# motor_dora.net
KiCad netlist of a schematic drawn in EAGLE
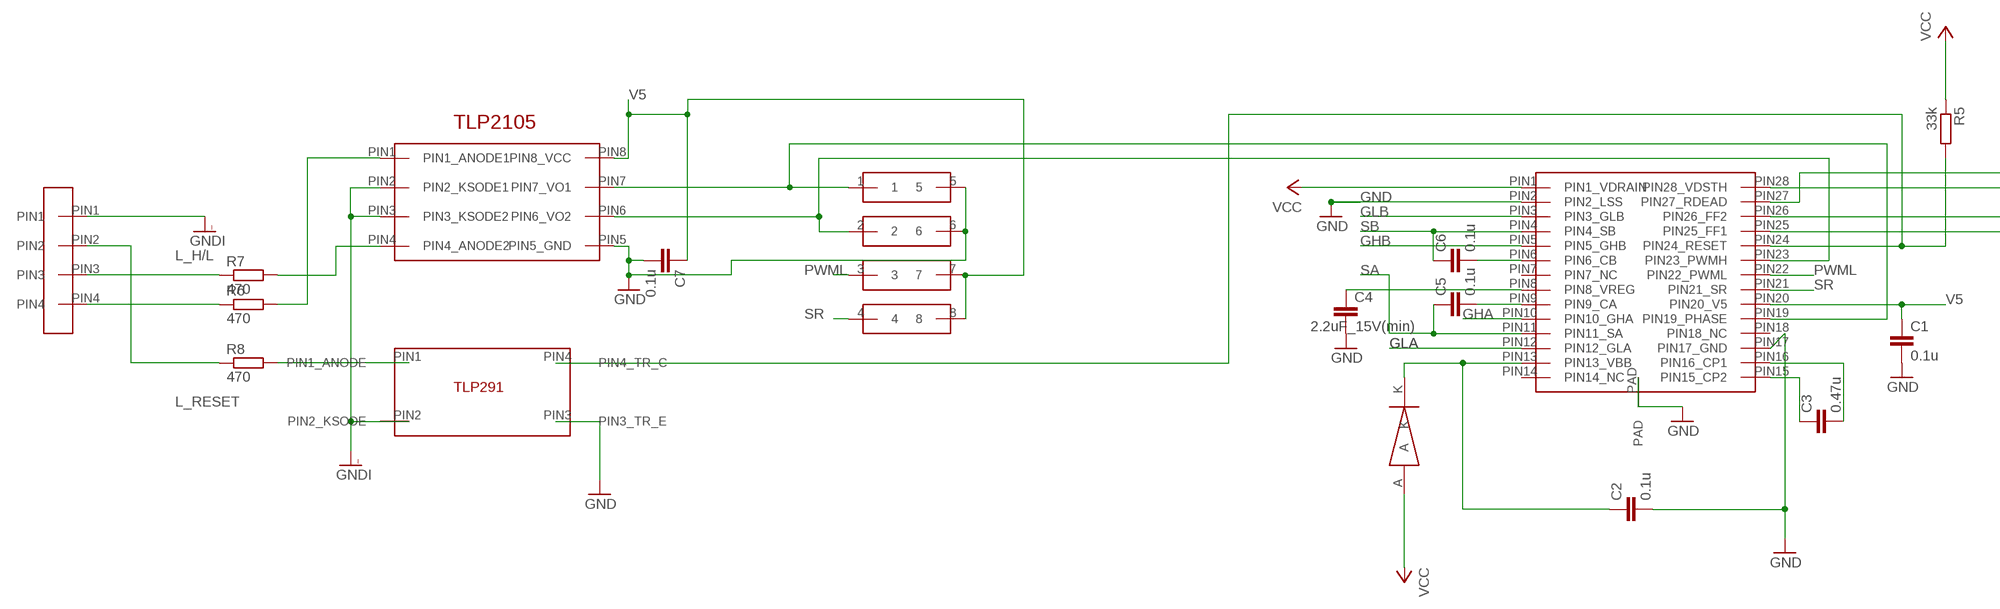
[diagram p0: schematic, sheet 1, part 1 of 2]
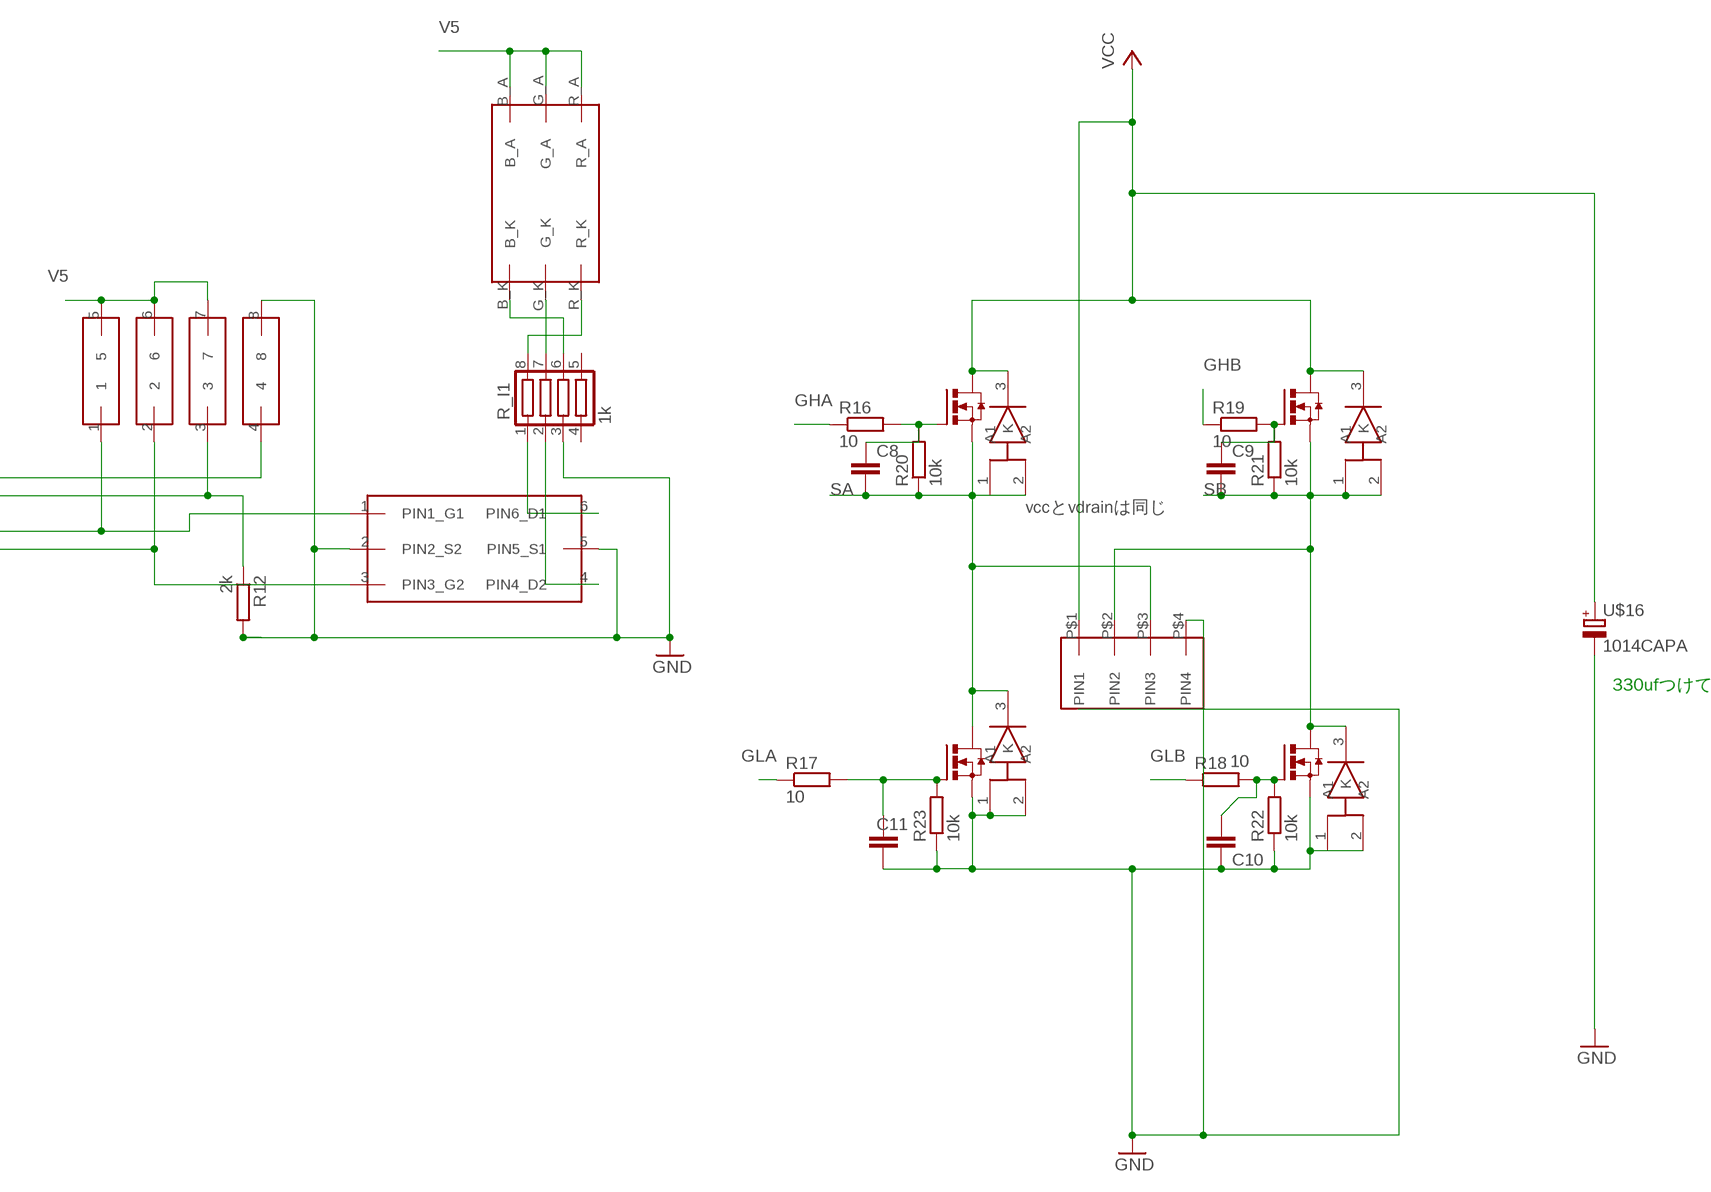
[diagram p1: schematic, sheet 1, part 2 of 2]

(export (version "E")
  (design (tool "Eeschema 10.0.6"))
  (components
    (comp (ref "C1")
      (value "0.1u")
      (footprint "eagle-import:C2012")
      (libsource (lib "eagle-import") (part "C-EUC2012"))
    )
    (comp (ref "C2")
      (value "0.1u")
      (footprint "eagle-import:C2012")
      (libsource (lib "eagle-import") (part "C-EUC2012"))
    )
    (comp (ref "C3")
      (value "0.47u")
      (footprint "eagle-import:C2012")
      (libsource (lib "eagle-import") (part "C-EUC2012"))
    )
    (comp (ref "C4")
      (value "2.2uF_15V(min)")
      (footprint "eagle-import:C2012")
      (libsource (lib "eagle-import") (part "C-EUC2012"))
    )
    (comp (ref "C5")
      (value "0.1u")
      (footprint "eagle-import:C2012")
      (libsource (lib "eagle-import") (part "C-EUC2012"))
    )
    (comp (ref "C6")
      (value "0.1u")
      (footprint "eagle-import:C2012")
      (libsource (lib "eagle-import") (part "C-EUC2012"))
    )
    (comp (ref "C7")
      (value "0.1u")
      (footprint "eagle-import:C2012")
      (libsource (lib "eagle-import") (part "C-EUC2012"))
    )
    (comp (ref "C8")
      (value "C-EUC2012")
      (footprint "eagle-import:C2012")
      (libsource (lib "eagle-import") (part "C-EUC2012"))
    )
    (comp (ref "C9")
      (value "C-EUC2012")
      (footprint "eagle-import:C2012")
      (libsource (lib "eagle-import") (part "C-EUC2012"))
    )
    (comp (ref "C10")
      (value "C-EUC2012")
      (footprint "eagle-import:C2012")
      (libsource (lib "eagle-import") (part "C-EUC2012"))
    )
    (comp (ref "C11")
      (value "C-EUC2012")
      (footprint "eagle-import:C2012")
      (libsource (lib "eagle-import") (part "C-EUC2012"))
    )
    (comp (ref "R5")
      (value "33k")
      (footprint "eagle-import:R2012")
      (libsource (lib "eagle-import") (part "R-EU_R2012"))
    )
    (comp (ref "R6")
      (value "470")
      (footprint "eagle-import:R2012")
      (libsource (lib "eagle-import") (part "R-EU_R2012"))
    )
    (comp (ref "R7")
      (value "470")
      (footprint "eagle-import:R2012")
      (libsource (lib "eagle-import") (part "R-EU_R2012"))
    )
    (comp (ref "R8")
      (value "470")
      (footprint "eagle-import:R2012")
      (libsource (lib "eagle-import") (part "R-EU_R2012"))
    )
    (comp (ref "R12")
      (value "2k")
      (footprint "eagle-import:R2012")
      (libsource (lib "eagle-import") (part "R-EU_R2012"))
    )
    (comp (ref "R16")
      (value "10")
      (footprint "eagle-import:R2012")
      (libsource (lib "eagle-import") (part "R-EU_R2012"))
    )
    (comp (ref "R17")
      (value "10")
      (footprint "eagle-import:R2012")
      (libsource (lib "eagle-import") (part "R-EU_R2012"))
    )
    (comp (ref "R18")
      (value "10")
      (footprint "eagle-import:R2012")
      (libsource (lib "eagle-import") (part "R-EU_R2012"))
    )
    (comp (ref "R19")
      (value "10")
      (footprint "eagle-import:R2012")
      (libsource (lib "eagle-import") (part "R-EU_R2012"))
    )
    (comp (ref "R20")
      (value "10k")
      (footprint "eagle-import:R2012")
      (libsource (lib "eagle-import") (part "R-EU_R2012"))
    )
    (comp (ref "R21")
      (value "10k")
      (footprint "eagle-import:R2012")
      (libsource (lib "eagle-import") (part "R-EU_R2012"))
    )
    (comp (ref "R22")
      (value "10k")
      (footprint "eagle-import:R2012")
      (libsource (lib "eagle-import") (part "R-EU_R2012"))
    )
    (comp (ref "R23")
      (value "10k")
      (footprint "eagle-import:R2012")
      (libsource (lib "eagle-import") (part "R-EU_R2012"))
    )
    (comp (ref "R_I1")
      (value "1k")
      (footprint "eagle-import:0603X4RESISTOR")
      (libsource (lib "eagle-import") (part "R_SHUGOU"))
    )
    (comp (ref "U$1")
      (value "A3921")
      (footprint "eagle-import:A3921")
      (libsource (lib "eagle-import") (part "A3921"))
    )
    (comp (ref "U$2")
      (value "TLP2105")
      (footprint "eagle-import:TLP2105")
      (libsource (lib "eagle-import") (part "TLP2105"))
    )
    (comp (ref "U$3")
      (value "TLP291")
      (footprint "eagle-import:TLP291")
      (libsource (lib "eagle-import") (part "TLP291"))
    )
    (comp (ref "U$4")
      (value "RGB_LED")
      (footprint "eagle-import:RGB_LED")
      (libsource (lib "eagle-import") (part "RGB_LED"))
    )
    (comp (ref "U$5")
      (value "10k")
      (footprint "eagle-import:1005X4RESISTOR")
      (libsource (lib "eagle-import") (part "1005X4RESISTOR"))
    )
    (comp (ref "U$6")
      (value "10k")
      (footprint "eagle-import:1005X4RESISTOR")
      (libsource (lib "eagle-import") (part "1005X4RESISTOR"))
    )
    (comp (ref "U$7")
      (value "SBR10M100P5Q")
      (footprint "eagle-import:POWERDI_5")
      (libsource (lib "eagle-import") (part "SBR10M100P5Q"))
    )
    (comp (ref "U$8")
      (value "IPD034N06N3G")
      (footprint "eagle-import:TO252")
      (libsource (lib "eagle-import") (part "IPD034N06N3G"))
    )
    (comp (ref "U$9")
      (value "IPD034N06N3G")
      (footprint "eagle-import:TO252")
      (libsource (lib "eagle-import") (part "IPD034N06N3G"))
    )
    (comp (ref "U$10")
      (value "IPD034N06N3G")
      (footprint "eagle-import:TO252")
      (libsource (lib "eagle-import") (part "IPD034N06N3G"))
    )
    (comp (ref "U$11")
      (value "IPD034N06N3G")
      (footprint "eagle-import:TO252")
      (libsource (lib "eagle-import") (part "IPD034N06N3G"))
    )
    (comp (ref "U$12")
      (value "SBR10M100P5Q")
      (footprint "eagle-import:POWERDI_5")
      (libsource (lib "eagle-import") (part "SBR10M100P5Q"))
    )
    (comp (ref "U$13")
      (value "DF1B_L_4P")
      (footprint "eagle-import:DF1B_L_4P")
      (libsource (lib "eagle-import") (part "DF1B_L_4P"))
    )
    (comp (ref "U$14")
      (value "VL_4P")
      (footprint "eagle-import:VL_4P")
      (libsource (lib "eagle-import") (part "VL_4P"))
    )
    (comp (ref "U$15")
      (value "SBR10M100P5Q")
      (footprint "eagle-import:POWERDI_5")
      (libsource (lib "eagle-import") (part "SBR10M100P5Q"))
    )
    (comp (ref "U$16")
      (value "1014CAPA")
      (footprint "eagle-import:1014CAPA")
      (libsource (lib "eagle-import") (part "1014CAPA"))
    )
    (comp (ref "U$17")
      (value "SMD_DAIOD")
      (footprint "eagle-import:SMD_DAIOD")
      (libsource (lib "eagle-import") (part "SMD_DAIOD"))
    )
    (comp (ref "U$18")
      (value "SSOT6_FET")
      (footprint "eagle-import:SSOT6_FET")
      (libsource (lib "eagle-import") (part "SSOT6_FET"))
    )
    (comp (ref "U$19")
      (value "SBR10M100P5Q")
      (footprint "eagle-import:POWERDI_5")
      (libsource (lib "eagle-import") (part "SBR10M100P5Q"))
    )
  )
  (nets
    (net (code "1") (name "/GHA") (class "Default")
      (node (ref "R16") (pin "1") (pinfunction "1_1") (pintype "passive"))
      (node (ref "U$1") (pin "PIN10") (pinfunction "PIN10_GHA_PIN10") (pintype "bidirectional"))
    )
    (net (code "2") (name "/GHB") (class "Default")
      (node (ref "R19") (pin "1") (pinfunction "1_1") (pintype "passive"))
      (node (ref "U$1") (pin "PIN5") (pinfunction "PIN5_GHB_PIN5") (pintype "bidirectional"))
    )
    (net (code "3") (name "/GLA") (class "Default")
      (node (ref "R17") (pin "1") (pinfunction "1_1") (pintype "passive"))
      (node (ref "U$1") (pin "PIN12") (pinfunction "PIN12_GLA_PIN12") (pintype "bidirectional"))
    )
    (net (code "4") (name "/GLB") (class "Default")
      (node (ref "R18") (pin "1") (pinfunction "1_1") (pintype "passive"))
      (node (ref "U$1") (pin "PIN3") (pinfunction "PIN3_GLB_PIN3") (pintype "bidirectional"))
    )
    (net (code "5") (name "/L_H{slash}L") (class "Default")
      (node (ref "R7") (pin "1") (pinfunction "1_1") (pintype "passive"))
      (node (ref "U$13") (pin "PIN3") (pinfunction "PIN3_PIN3") (pintype "bidirectional"))
    )
    (net (code "6") (name "/L_RESET") (class "Default")
      (node (ref "R8") (pin "1") (pinfunction "1_1") (pintype "passive"))
      (node (ref "U$13") (pin "PIN2") (pinfunction "PIN2_PIN2") (pintype "bidirectional"))
    )
    (net (code "7") (name "/PWML") (class "Default")
      (node (ref "U$1") (pin "PIN22") (pinfunction "PIN22_PWML_PIN22") (pintype "bidirectional"))
      (node (ref "U$5") (pin "3") (pinfunction "3_3") (pintype "bidirectional"))
    )
    (net (code "8") (name "/SA") (class "Default")
      (node (ref "C5") (pin "1") (pinfunction "1_1") (pintype "passive"))
      (node (ref "C8") (pin "2") (pinfunction "2_2") (pintype "passive"))
      (node (ref "R20") (pin "1") (pinfunction "1_1") (pintype "passive"))
      (node (ref "U$1") (pin "PIN11") (pinfunction "PIN11_SA_PIN11") (pintype "bidirectional"))
      (node (ref "U$10") (pin "PIN2") (pinfunction "PIN2_D_PIN2") (pintype "passive"))
      (node (ref "U$14") (pin "P$3") (pinfunction "PIN3_P$3") (pintype "bidirectional"))
      (node (ref "U$19") (pin "1") (pinfunction "A1_1") (pintype "bidirectional"))
      (node (ref "U$19") (pin "2") (pinfunction "A2_2") (pintype "bidirectional"))
      (node (ref "U$7") (pin "3") (pinfunction "K_3") (pintype "bidirectional"))
      (node (ref "U$8") (pin "PIN3") (pinfunction "PIN3_S_PIN3") (pintype "passive"))
    )
    (net (code "9") (name "/SB") (class "Default")
      (node (ref "C6") (pin "1") (pinfunction "1_1") (pintype "passive"))
      (node (ref "C9") (pin "2") (pinfunction "2_2") (pintype "passive"))
      (node (ref "R21") (pin "1") (pinfunction "1_1") (pintype "passive"))
      (node (ref "U$1") (pin "PIN4") (pinfunction "PIN4_SB_PIN4") (pintype "bidirectional"))
      (node (ref "U$11") (pin "PIN2") (pinfunction "PIN2_D_PIN2") (pintype "passive"))
      (node (ref "U$12") (pin "3") (pinfunction "K_3") (pintype "bidirectional"))
      (node (ref "U$14") (pin "P$2") (pinfunction "PIN2_P$2") (pintype "bidirectional"))
      (node (ref "U$15") (pin "1") (pinfunction "A1_1") (pintype "bidirectional"))
      (node (ref "U$15") (pin "2") (pinfunction "A2_2") (pintype "bidirectional"))
      (node (ref "U$9") (pin "PIN3") (pinfunction "PIN3_S_PIN3") (pintype "passive"))
    )
    (net (code "10") (name "/SR") (class "Default")
      (node (ref "U$1") (pin "PIN21") (pinfunction "PIN21_SR_PIN21") (pintype "bidirectional"))
      (node (ref "U$5") (pin "4") (pinfunction "4_4") (pintype "bidirectional"))
    )
    (net (code "11") (name "/V5") (class "Default")
      (node (ref "C1") (pin "1") (pinfunction "1_1") (pintype "passive"))
      (node (ref "C7") (pin "1") (pinfunction "1_1") (pintype "passive"))
      (node (ref "U$1") (pin "PIN20") (pinfunction "PIN20_V5_PIN20") (pintype "bidirectional"))
      (node (ref "U$2") (pin "PIN8") (pinfunction "PIN8_VCC_PIN8") (pintype "bidirectional"))
      (node (ref "U$4") (pin "B_A") (pinfunction "B_A_B_A") (pintype "bidirectional"))
      (node (ref "U$4") (pin "G_A") (pinfunction "G_A_G_A") (pintype "bidirectional"))
      (node (ref "U$4") (pin "R_A") (pinfunction "R_A_R_A") (pintype "bidirectional"))
      (node (ref "U$5") (pin "7") (pinfunction "7_7") (pintype "bidirectional"))
      (node (ref "U$5") (pin "8") (pinfunction "8_8") (pintype "bidirectional"))
      (node (ref "U$6") (pin "5") (pinfunction "5_5") (pintype "bidirectional"))
      (node (ref "U$6") (pin "6") (pinfunction "6_6") (pintype "bidirectional"))
      (node (ref "U$6") (pin "7") (pinfunction "7_7") (pintype "bidirectional"))
    )
    (net (code "12") (name "GND") (class "Default")
      (node (ref "C1") (pin "2") (pinfunction "2_2") (pintype "passive"))
      (node (ref "C10") (pin "2") (pinfunction "2_2") (pintype "passive"))
      (node (ref "C11") (pin "2") (pinfunction "2_2") (pintype "passive"))
      (node (ref "C2") (pin "2") (pinfunction "2_2") (pintype "passive"))
      (node (ref "C4") (pin "2") (pinfunction "2_2") (pintype "passive"))
      (node (ref "C7") (pin "2") (pinfunction "2_2") (pintype "passive"))
      (node (ref "R12") (pin "2") (pinfunction "2_2") (pintype "passive"))
      (node (ref "R22") (pin "1") (pinfunction "1_1") (pintype "passive"))
      (node (ref "R23") (pin "1") (pinfunction "1_1") (pintype "passive"))
      (node (ref "R_I1") (pin "3") (pinfunction "3_3") (pintype "passive"))
      (node (ref "U$1") (pin "PAD") (pinfunction "PAD_PAD") (pintype "bidirectional"))
      (node (ref "U$1") (pin "PIN17") (pinfunction "PIN17_GND_PIN17") (pintype "bidirectional"))
      (node (ref "U$1") (pin "PIN2") (pinfunction "PIN2_LSS_PIN2") (pintype "bidirectional"))
      (node (ref "U$10") (pin "PIN3") (pinfunction "PIN3_S_PIN3") (pintype "passive"))
      (node (ref "U$11") (pin "PIN3") (pinfunction "PIN3_S_PIN3") (pintype "passive"))
      (node (ref "U$12") (pin "1") (pinfunction "A1_1") (pintype "bidirectional"))
      (node (ref "U$12") (pin "2") (pinfunction "A2_2") (pintype "bidirectional"))
      (node (ref "U$14") (pin "P$4") (pinfunction "PIN4_P$4") (pintype "bidirectional"))
      (node (ref "U$16") (pin "-") (pinfunction "-_-") (pintype "passive"))
      (node (ref "U$18") (pin "2") (pinfunction "PIN2_S2_2") (pintype "bidirectional"))
      (node (ref "U$18") (pin "5") (pinfunction "PIN5_S1_5") (pintype "bidirectional"))
      (node (ref "U$2") (pin "PIN5") (pinfunction "PIN5_GND_PIN5") (pintype "bidirectional"))
      (node (ref "U$3") (pin "PIN3") (pinfunction "PIN3_TR_E_PIN3") (pintype "bidirectional"))
      (node (ref "U$5") (pin "5") (pinfunction "5_5") (pintype "bidirectional"))
      (node (ref "U$5") (pin "6") (pinfunction "6_6") (pintype "bidirectional"))
      (node (ref "U$6") (pin "8") (pinfunction "8_8") (pintype "bidirectional"))
      (node (ref "U$7") (pin "1") (pinfunction "A1_1") (pintype "bidirectional"))
      (node (ref "U$7") (pin "2") (pinfunction "A2_2") (pintype "bidirectional"))
    )
    (net (code "13") (name "GNDI") (class "Default")
      (node (ref "U$13") (pin "PIN1") (pinfunction "PIN1_PIN1") (pintype "bidirectional"))
      (node (ref "U$2") (pin "PIN2") (pinfunction "PIN2_KSODE1_PIN2") (pintype "bidirectional"))
      (node (ref "U$2") (pin "PIN3") (pinfunction "PIN3_KSODE2_PIN3") (pintype "bidirectional"))
      (node (ref "U$3") (pin "PIN2") (pinfunction "PIN2_KSODE_PIN2") (pintype "bidirectional"))
    )
    (net (code "14") (name "Net-(R6-Pad1)") (class "Default")
      (node (ref "R6") (pin "1") (pinfunction "1_1") (pintype "passive"))
      (node (ref "U$13") (pin "PIN4") (pinfunction "PIN4_PIN4") (pintype "bidirectional"))
    )
    (net (code "15") (name "Net-(R_I1-Pad6)") (class "Default")
      (node (ref "R_I1") (pin "6") (pinfunction "6_6") (pintype "passive"))
      (node (ref "U$4") (pin "B_K") (pinfunction "B_K_B_K") (pintype "bidirectional"))
    )
    (net (code "16") (name "Net-(R_I1-Pad7)") (class "Default")
      (node (ref "R_I1") (pin "7") (pinfunction "7_7") (pintype "passive"))
      (node (ref "U$4") (pin "G_K") (pinfunction "G_K_G_K") (pintype "bidirectional"))
    )
    (net (code "17") (name "Net-(R_I1-Pad8)") (class "Default")
      (node (ref "R_I1") (pin "8") (pinfunction "8_8") (pintype "passive"))
      (node (ref "U$4") (pin "R_K") (pinfunction "R_K_R_K") (pintype "bidirectional"))
    )
    (net (code "18") (name "Net-(U$1-PIN6_CB)") (class "Default")
      (node (ref "C6") (pin "2") (pinfunction "2_2") (pintype "passive"))
      (node (ref "U$1") (pin "PIN6") (pinfunction "PIN6_CB_PIN6") (pintype "bidirectional"))
    )
    (net (code "19") (name "Net-(U$1-PIN8_VREG)") (class "Default")
      (node (ref "C4") (pin "1") (pinfunction "1_1") (pintype "passive"))
      (node (ref "U$1") (pin "PIN8") (pinfunction "PIN8_VREG_PIN8") (pintype "bidirectional"))
    )
    (net (code "20") (name "Net-(U$1-PIN9_CA)") (class "Default")
      (node (ref "C5") (pin "2") (pinfunction "2_2") (pintype "passive"))
      (node (ref "U$1") (pin "PIN9") (pinfunction "PIN9_CA_PIN9") (pintype "bidirectional"))
    )
    (net (code "21") (name "Net-(U$1-PIN13_VBB)") (class "Default")
      (node (ref "C2") (pin "1") (pinfunction "1_1") (pintype "passive"))
      (node (ref "U$1") (pin "PIN13") (pinfunction "PIN13_VBB_PIN13") (pintype "bidirectional"))
      (node (ref "U$17") (pin "K") (pinfunction "K_K") (pintype "bidirectional"))
    )
    (net (code "22") (name "Net-(U$1-PIN15_CP2)") (class "Default")
      (node (ref "C3") (pin "1") (pinfunction "1_1") (pintype "passive"))
      (node (ref "U$1") (pin "PIN15") (pinfunction "PIN15_CP2_PIN15") (pintype "bidirectional"))
    )
    (net (code "23") (name "Net-(U$1-PIN16_CP1)") (class "Default")
      (node (ref "C3") (pin "2") (pinfunction "2_2") (pintype "passive"))
      (node (ref "U$1") (pin "PIN16") (pinfunction "PIN16_CP1_PIN16") (pintype "bidirectional"))
    )
    (net (code "24") (name "Net-(U$1-PIN19_PHASE)") (class "Default")
      (node (ref "U$1") (pin "PIN19") (pinfunction "PIN19_PHASE_PIN19") (pintype "bidirectional"))
      (node (ref "U$2") (pin "PIN7") (pinfunction "PIN7_VO1_PIN7") (pintype "bidirectional"))
      (node (ref "U$5") (pin "1") (pinfunction "1_1") (pintype "bidirectional"))
    )
    (net (code "25") (name "Net-(U$1-PIN23_PWMH)") (class "Default")
      (node (ref "U$1") (pin "PIN23") (pinfunction "PIN23_PWMH_PIN23") (pintype "bidirectional"))
      (node (ref "U$2") (pin "PIN6") (pinfunction "PIN6_VO2_PIN6") (pintype "bidirectional"))
      (node (ref "U$5") (pin "2") (pinfunction "2_2") (pintype "bidirectional"))
    )
    (net (code "26") (name "Net-(U$1-PIN24_RESET)") (class "Default")
      (node (ref "R5") (pin "2") (pinfunction "2_2") (pintype "passive"))
      (node (ref "U$1") (pin "PIN24") (pinfunction "PIN24_RESET_PIN24") (pintype "bidirectional"))
      (node (ref "U$3") (pin "PIN4") (pinfunction "PIN4_TR_C_PIN4") (pintype "bidirectional"))
    )
    (net (code "27") (name "Net-(U$1-PIN25_FF1)") (class "Default")
      (node (ref "U$1") (pin "PIN25") (pinfunction "PIN25_FF1_PIN25") (pintype "bidirectional"))
      (node (ref "U$18") (pin "3") (pinfunction "PIN3_G2_3") (pintype "bidirectional"))
      (node (ref "U$6") (pin "2") (pinfunction "2_2") (pintype "bidirectional"))
    )
    (net (code "28") (name "Net-(U$1-PIN26_FF2)") (class "Default")
      (node (ref "U$1") (pin "PIN26") (pinfunction "PIN26_FF2_PIN26") (pintype "bidirectional"))
      (node (ref "U$18") (pin "1") (pinfunction "PIN1_G1_1") (pintype "bidirectional"))
      (node (ref "U$6") (pin "1") (pinfunction "1_1") (pintype "bidirectional"))
    )
    (net (code "29") (name "Net-(U$1-PIN27_RDEAD)") (class "Default")
      (node (ref "U$1") (pin "PIN27") (pinfunction "PIN27_RDEAD_PIN27") (pintype "bidirectional"))
      (node (ref "U$6") (pin "4") (pinfunction "4_4") (pintype "bidirectional"))
    )
    (net (code "30") (name "Net-(U$1-PIN28_VDSTH)") (class "Default")
      (node (ref "R12") (pin "1") (pinfunction "1_1") (pintype "passive"))
      (node (ref "U$1") (pin "PIN28") (pinfunction "PIN28_VDSTH_PIN28") (pintype "bidirectional"))
      (node (ref "U$6") (pin "3") (pinfunction "3_3") (pintype "bidirectional"))
    )
    (net (code "31") (name "Net-(U$2-PIN1_ANODE1)") (class "Default")
      (node (ref "R6") (pin "2") (pinfunction "2_2") (pintype "passive"))
      (node (ref "U$2") (pin "PIN1") (pinfunction "PIN1_ANODE1_PIN1") (pintype "bidirectional"))
    )
    (net (code "32") (name "Net-(U$2-PIN4_ANODE2)") (class "Default")
      (node (ref "R7") (pin "2") (pinfunction "2_2") (pintype "passive"))
      (node (ref "U$2") (pin "PIN4") (pinfunction "PIN4_ANODE2_PIN4") (pintype "bidirectional"))
    )
    (net (code "33") (name "Net-(U$3-PIN1_ANODE)") (class "Default")
      (node (ref "R8") (pin "2") (pinfunction "2_2") (pintype "passive"))
      (node (ref "U$3") (pin "PIN1") (pinfunction "PIN1_ANODE_PIN1") (pintype "bidirectional"))
    )
    (net (code "34") (name "Net-(U$8-PIN1_G)") (class "Default")
      (node (ref "C8") (pin "1") (pinfunction "1_1") (pintype "passive"))
      (node (ref "R16") (pin "2") (pinfunction "2_2") (pintype "passive"))
      (node (ref "R20") (pin "2") (pinfunction "2_2") (pintype "passive"))
      (node (ref "U$8") (pin "PIN1") (pinfunction "PIN1_G_PIN1") (pintype "passive"))
    )
    (net (code "35") (name "Net-(U$9-PIN1_G)") (class "Default")
      (node (ref "C9") (pin "1") (pinfunction "1_1") (pintype "passive"))
      (node (ref "R19") (pin "2") (pinfunction "2_2") (pintype "passive"))
      (node (ref "R21") (pin "2") (pinfunction "2_2") (pintype "passive"))
      (node (ref "U$9") (pin "PIN1") (pinfunction "PIN1_G_PIN1") (pintype "passive"))
    )
    (net (code "36") (name "Net-(U$10-PIN1_G)") (class "Default")
      (node (ref "C11") (pin "1") (pinfunction "1_1") (pintype "passive"))
      (node (ref "R17") (pin "2") (pinfunction "2_2") (pintype "passive"))
      (node (ref "R23") (pin "2") (pinfunction "2_2") (pintype "passive"))
      (node (ref "U$10") (pin "PIN1") (pinfunction "PIN1_G_PIN1") (pintype "passive"))
    )
    (net (code "37") (name "Net-(U$11-PIN1_G)") (class "Default")
      (node (ref "C10") (pin "1") (pinfunction "1_1") (pintype "passive"))
      (node (ref "R18") (pin "2") (pinfunction "2_2") (pintype "passive"))
      (node (ref "R22") (pin "2") (pinfunction "2_2") (pintype "passive"))
      (node (ref "U$11") (pin "PIN1") (pinfunction "PIN1_G_PIN1") (pintype "passive"))
    )
    (net (code "38") (name "Net-(U$18-PIN4_D2)") (class "Default")
      (node (ref "R_I1") (pin "2") (pinfunction "2_2") (pintype "passive"))
      (node (ref "U$18") (pin "4") (pinfunction "PIN4_D2_4") (pintype "bidirectional"))
    )
    (net (code "39") (name "Net-(U$18-PIN6_D1)") (class "Default")
      (node (ref "R_I1") (pin "1") (pinfunction "1_1") (pintype "passive"))
      (node (ref "U$18") (pin "6") (pinfunction "PIN6_D1_6") (pintype "bidirectional"))
    )
    (net (code "40") (name "VCC") (class "Default")
      (node (ref "R5") (pin "1") (pinfunction "1_1") (pintype "passive"))
      (node (ref "U$1") (pin "PIN1") (pinfunction "PIN1_VDRAIN_PIN1") (pintype "bidirectional"))
      (node (ref "U$14") (pin "P$1") (pinfunction "PIN1_P$1") (pintype "bidirectional"))
      (node (ref "U$15") (pin "3") (pinfunction "K_3") (pintype "bidirectional"))
      (node (ref "U$16") (pin "+") (pinfunction "+_+") (pintype "passive"))
      (node (ref "U$17") (pin "A") (pinfunction "A_A") (pintype "bidirectional"))
      (node (ref "U$19") (pin "3") (pinfunction "K_3") (pintype "bidirectional"))
      (node (ref "U$8") (pin "PIN2") (pinfunction "PIN2_D_PIN2") (pintype "passive"))
      (node (ref "U$9") (pin "PIN2") (pinfunction "PIN2_D_PIN2") (pintype "passive"))
    )
    (net (code "41") (name "unconnected-(R_I1-Pad4)") (class "Default")
      (node (ref "R_I1") (pin "4") (pinfunction "4_4") (pintype "passive"))
    )
    (net (code "42") (name "unconnected-(R_I1-Pad5)") (class "Default")
      (node (ref "R_I1") (pin "5") (pinfunction "5_5") (pintype "passive"))
    )
    (net (code "43") (name "unconnected-(U$1-PIN7_NC-PadPIN7)") (class "Default")
      (node (ref "U$1") (pin "PIN7") (pinfunction "PIN7_NC_PIN7") (pintype "bidirectional"))
    )
    (net (code "44") (name "unconnected-(U$1-PIN14_NC-PadPIN14)") (class "Default")
      (node (ref "U$1") (pin "PIN14") (pinfunction "PIN14_NC_PIN14") (pintype "bidirectional"))
    )
    (net (code "45") (name "unconnected-(U$1-PIN18_NC-PadPIN18)") (class "Default")
      (node (ref "U$1") (pin "PIN18") (pinfunction "PIN18_NC_PIN18") (pintype "bidirectional"))
    )
  )
)
